# IS62LV1024.net
KiCad netlist of a schematic drawn in Altium Designer
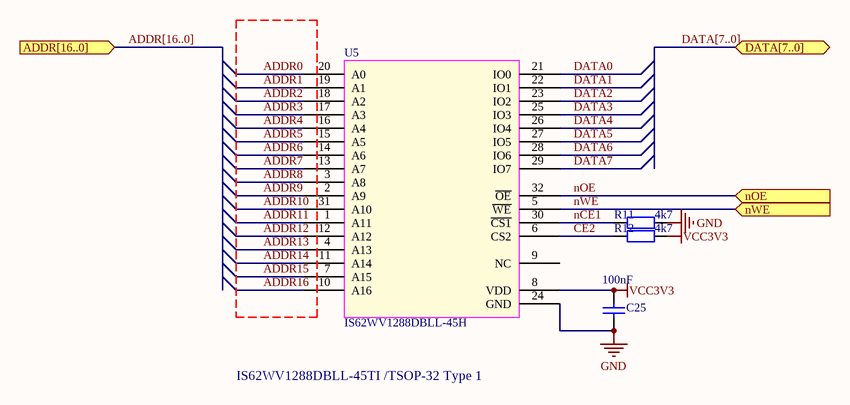
[diagram p0: IS62LV1024.SchDoc]

(export (version "E")
  (design (tool "Eeschema 10.0.6"))
  (components
    (comp (ref "C25") (value "100nF") (footprint "R0603") (libsource (lib "MyYX") (part "CAP_04")))
    (comp (ref "R11") (value "4k7") (footprint "R0603") (libsource (lib "MyYX") (part "RES_04")))
    (comp (ref "R12") (value "4k7") (footprint "R0603") (libsource (lib "MyYX") (part "RES_04")))
    (comp (ref "U5")
      (value "IS62WV1288DBLL-45H")
      (footprint "sTSOP32")
      (description "128Kx8 LOW VOLTAGE,ULTRA LOW POWER SRAM")
      (libsource (lib "MyYX") (part "IS62WV1288DBLL-45TLI/TSOP-32"))
    )
  )
  (nets
    (net (code "1") (name "/ADDR0") (class "Default")
      (node (ref "U5") (pin "20") (pinfunction "A0_20") (pintype "passive"))
    )
    (net (code "2") (name "/ADDR1") (class "Default")
      (node (ref "U5") (pin "19") (pinfunction "A1_19") (pintype "passive"))
    )
    (net (code "3") (name "/ADDR2") (class "Default")
      (node (ref "U5") (pin "18") (pinfunction "A2_18") (pintype "passive"))
    )
    (net (code "4") (name "/ADDR3") (class "Default")
      (node (ref "U5") (pin "17") (pinfunction "A3_17") (pintype "passive"))
    )
    (net (code "5") (name "/ADDR4") (class "Default")
      (node (ref "U5") (pin "16") (pinfunction "A4_16") (pintype "passive"))
    )
    (net (code "6") (name "/ADDR5") (class "Default")
      (node (ref "U5") (pin "15") (pinfunction "A5_15") (pintype "passive"))
    )
    (net (code "7") (name "/ADDR6") (class "Default")
      (node (ref "U5") (pin "14") (pinfunction "A6_14") (pintype "passive"))
    )
    (net (code "8") (name "/ADDR7") (class "Default")
      (node (ref "U5") (pin "13") (pinfunction "A7_13") (pintype "passive"))
    )
    (net (code "9") (name "/ADDR8") (class "Default")
      (node (ref "U5") (pin "3") (pinfunction "A8_3") (pintype "passive"))
    )
    (net (code "10") (name "/ADDR9") (class "Default")
      (node (ref "U5") (pin "2") (pinfunction "A9_2") (pintype "passive"))
    )
    (net (code "11") (name "/ADDR10") (class "Default")
      (node (ref "U5") (pin "31") (pinfunction "A10_31") (pintype "passive"))
    )
    (net (code "12") (name "/ADDR11") (class "Default")
      (node (ref "U5") (pin "1") (pinfunction "A11_1") (pintype "passive"))
    )
    (net (code "13") (name "/ADDR12") (class "Default")
      (node (ref "U5") (pin "12") (pinfunction "A12_12") (pintype "passive"))
    )
    (net (code "14") (name "/ADDR13") (class "Default")
      (node (ref "U5") (pin "4") (pinfunction "A13_4") (pintype "passive"))
    )
    (net (code "15") (name "/ADDR14") (class "Default")
      (node (ref "U5") (pin "11") (pinfunction "A14_11") (pintype "passive"))
    )
    (net (code "16") (name "/ADDR15") (class "Default")
      (node (ref "U5") (pin "7") (pinfunction "A15_7") (pintype "passive"))
    )
    (net (code "17") (name "/ADDR16") (class "Default")
      (node (ref "U5") (pin "10") (pinfunction "A16_10") (pintype "passive"))
    )
    (net (code "19") (name "/CE2") (class "Default")
      (node (ref "R12") (pin "1") (pinfunction "1_1") (pintype "passive"))
      (node (ref "U5") (pin "6") (pinfunction "CS2_6") (pintype "passive"))
    )
    (net (code "20") (name "/DATA0") (class "Default")
      (node (ref "U5") (pin "21") (pinfunction "IO0_21") (pintype "passive"))
    )
    (net (code "21") (name "/DATA1") (class "Default")
      (node (ref "U5") (pin "22") (pinfunction "IO1_22") (pintype "passive"))
    )
    (net (code "22") (name "/DATA2") (class "Default")
      (node (ref "U5") (pin "23") (pinfunction "IO2_23") (pintype "passive"))
    )
    (net (code "23") (name "/DATA3") (class "Default")
      (node (ref "U5") (pin "25") (pinfunction "IO3_25") (pintype "passive"))
    )
    (net (code "24") (name "/DATA4") (class "Default")
      (node (ref "U5") (pin "26") (pinfunction "IO4_26") (pintype "passive"))
    )
    (net (code "25") (name "/DATA5") (class "Default")
      (node (ref "U5") (pin "27") (pinfunction "IO5_27") (pintype "passive"))
    )
    (net (code "26") (name "/DATA6") (class "Default")
      (node (ref "U5") (pin "28") (pinfunction "IO6_28") (pintype "passive"))
    )
    (net (code "27") (name "/DATA7") (class "Default")
      (node (ref "U5") (pin "29") (pinfunction "IO7_29") (pintype "passive"))
    )
    (net (code "29") (name "/nCE1") (class "Default")
      (node (ref "R11") (pin "1") (pinfunction "1_1") (pintype "passive"))
      (node (ref "U5") (pin "30") (pinfunction "~{CS1}_30") (pintype "passive"))
    )
    (net (code "30") (name "/nOE") (class "Default")
      (node (ref "U5") (pin "32") (pinfunction "~{OE}_32") (pintype "passive"))
    )
    (net (code "31") (name "/nWE") (class "Default")
      (node (ref "U5") (pin "5") (pinfunction "~{WE}_5") (pintype "passive"))
    )
    (net (code "32") (name "GND") (class "Default")
      (node (ref "C25") (pin "1") (pinfunction "1_1") (pintype "passive"))
      (node (ref "R11") (pin "2") (pinfunction "2_2") (pintype "passive"))
      (node (ref "U5") (pin "24") (pinfunction "GND_24") (pintype "passive"))
    )
    (net (code "33") (name "VCC3V3") (class "Default")
      (node (ref "C25") (pin "2") (pinfunction "2_2") (pintype "passive"))
      (node (ref "R12") (pin "2") (pinfunction "2_2") (pintype "passive"))
      (node (ref "U5") (pin "8") (pinfunction "VDD_8") (pintype "passive"))
    )
    (net (code "34") (name "unconnected-(U5-NC-Pad9)") (class "Default")
      (node (ref "U5") (pin "9") (pinfunction "NC_9") (pintype "passive"))
    )
  )
)
